# UI_Ticketing_Master.net
KiCad netlist of a schematic drawn in Altium Designer
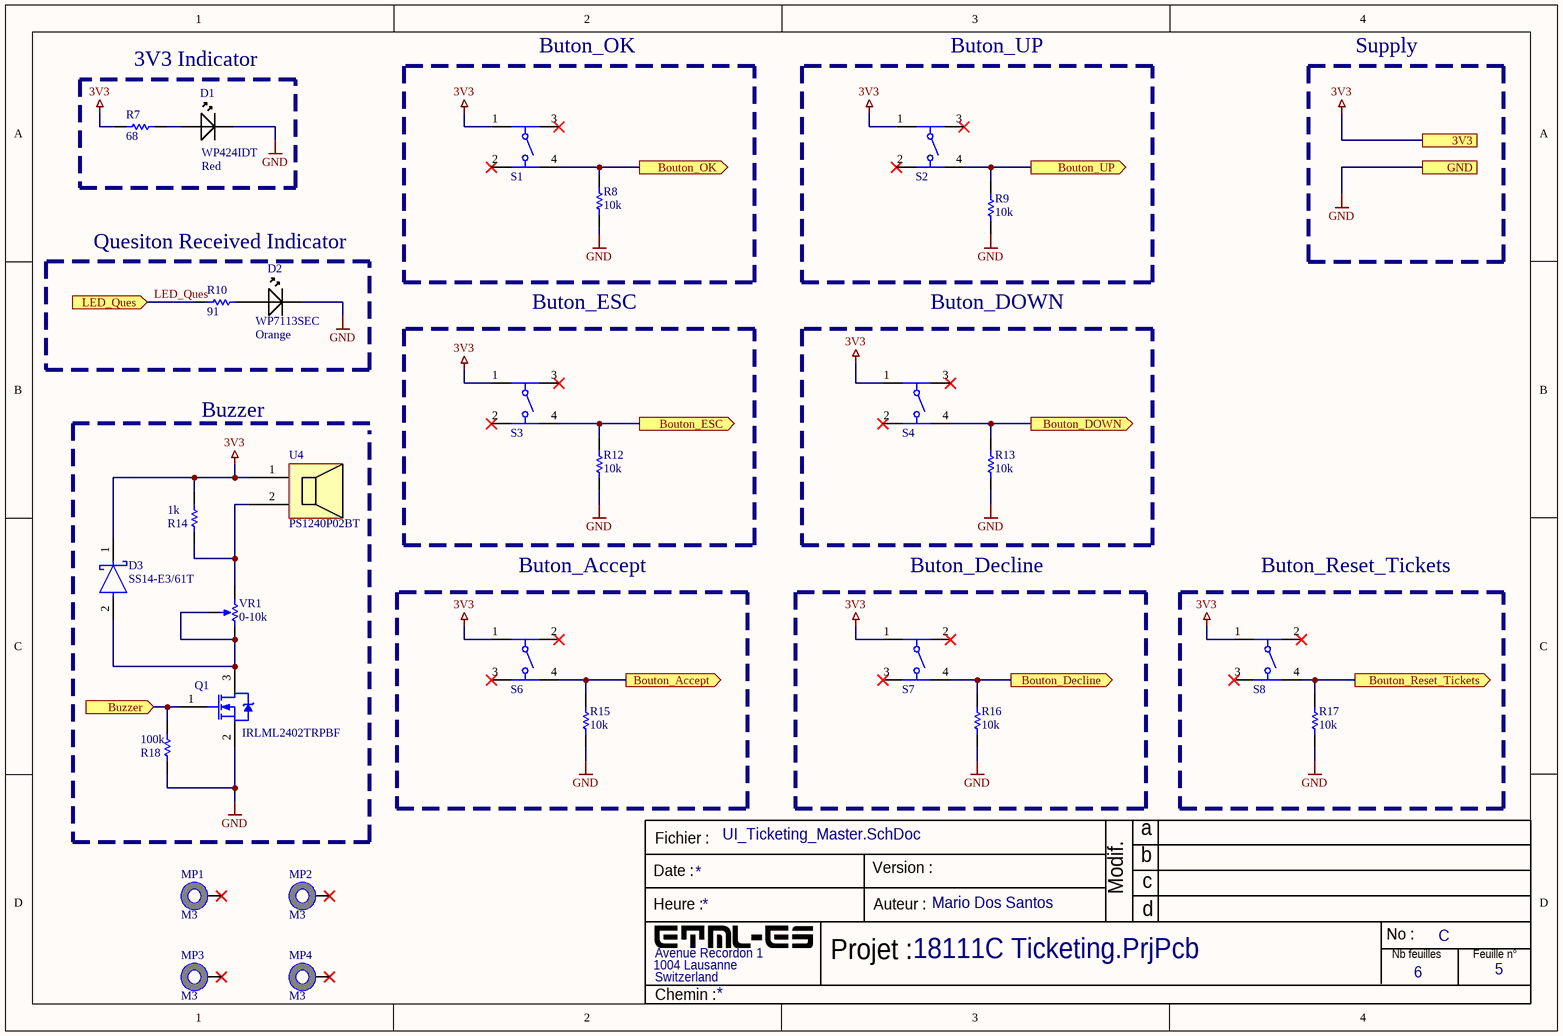
[diagram p0: UI_Ticketing_Master.SchDoc]

(export (version "E")
  (design (tool "Eeschema 10.0.6"))
  (components
    (comp (ref "D1")
      (value "WP424IDT")
      (footprint "LED-2P-2.28-3MM")
      (description "LED")
      (fields (field (name "COLOR") "Red"))
      (libsource (lib "") (part "LED_1"))
    )
    (comp (ref "D2")
      (value "WP7113SEC")
      (footprint "Type 5mm")
      (description "LED")
      (fields (field (name "COLOR") "Orange"))
      (libsource (lib "Spectrometre_Lib") (part "LED"))
    )
    (comp (ref "D3")
      (value "SS14-E3/61T")
      (footprint "FP-95400-MFG")
      (description "DIODE SCHOTTKY 40V 1A DO214AC")
      (fields
        (field (name "OCTOPART") "https://octopart.com/ss14-e3%2F61t-vishay-39552847")
        (field (name "MANUFACTURER") "Vishay")
      )
      (libsource (lib "Altium Content Vault") (part "1d6ec82d83fb6aee721767c19dac4b9"))
    )
    (comp (ref "MP1")
      (value "M3")
      (footprint "PCB_Ticketing_Master:9774010151")
      (description "WA-SMSI SMT Steel Spacer, M2.5 Thread Internal, Length 1mm")
      (libsource (lib "ALTIUM-SMSI_SMT_STEEL_SPACER_M2_5_THREAD_INTERNAL-rev16b") (part "9774010151"))
    )
    (comp (ref "MP2")
      (value "M3")
      (footprint "PCB_Ticketing_Master:9774010151")
      (description "WA-SMSI SMT Steel Spacer, M2.5 Thread Internal, Length 1mm")
      (libsource (lib "ALTIUM-SMSI_SMT_STEEL_SPACER_M2_5_THREAD_INTERNAL-rev16b") (part "9774010151"))
    )
    (comp (ref "MP3")
      (value "M3")
      (footprint "PCB_Ticketing_Master:9774010151")
      (description "WA-SMSI SMT Steel Spacer, M2.5 Thread Internal, Length 1mm")
      (libsource (lib "ALTIUM-SMSI_SMT_STEEL_SPACER_M2_5_THREAD_INTERNAL-rev16b") (part "9774010151"))
    )
    (comp (ref "MP4")
      (value "M3")
      (footprint "PCB_Ticketing_Master:9774010151")
      (description "WA-SMSI SMT Steel Spacer, M2.5 Thread Internal, Length 1mm")
      (libsource (lib "ALTIUM-SMSI_SMT_STEEL_SPACER_M2_5_THREAD_INTERNAL-rev16b") (part "9774010151"))
    )
    (comp (ref "Q1")
      (value "IRLML2402TRPBF")
      (footprint "INTR-IRLML2402TRPBF-3_V")
      (description "HEXFET(R) Power MOSFET, N-Channel, 20 V, 1.2 A, 3-Pin SOT-23, RoHS, Tape and Reel")
      (fields
        (field (name "MANUFACTURER") "Infineon Technologies")
        (field (name "PARTNUMBER") "IRLML2402TRBF")
      )
      (libsource (lib "Altium Content Vault") (part "CMP-2000-05155-1"))
    )
    (comp (ref "R7")
      (value "68")
      (footprint "RESC0805(2012)_L")
      (description "100K 0.125W 5% 0805 (2012 Metric)  SMD")
      (libsource (lib "Altium Content Vault") (part "CMP-1013-00122-1"))
    )
    (comp (ref "R8")
      (value "10k")
      (footprint "RESC0805(2012)_L")
      (description "100K 0.125W 5% 0805 (2012 Metric)  SMD")
      (fields (field (name "TOLERANCE") "5 %") (field (name "POWER") "0.125 W"))
      (libsource (lib "Altium Content Vault") (part "CMP-1013-00122-1"))
    )
    (comp (ref "R9")
      (value "10k")
      (footprint "RESC0805(2012)_L")
      (description "100K 0.125W 5% 0805 (2012 Metric)  SMD")
      (fields (field (name "TOLERANCE") "5 %") (field (name "POWER") "0.125 W"))
      (libsource (lib "Altium Content Vault") (part "CMP-1013-00122-1"))
    )
    (comp (ref "R10")
      (value "91")
      (footprint "RESC0805(2012)_L")
      (description "100K 0.125W 5% 0805 (2012 Metric)  SMD")
      (fields (field (name "TOLERANCE") "5 %") (field (name "POWER") "0.125 W"))
      (libsource (lib "Altium Content Vault") (part "CMP-1013-00122-1"))
    )
    (comp (ref "R12")
      (value "10k")
      (footprint "RESC0805(2012)_L")
      (description "100K 0.125W 5% 0805 (2012 Metric)  SMD")
      (fields (field (name "TOLERANCE") "5 %") (field (name "POWER") "0.125 W"))
      (libsource (lib "Altium Content Vault") (part "CMP-1013-00122-1"))
    )
    (comp (ref "R13")
      (value "10k")
      (footprint "RESC0805(2012)_L")
      (description "100K 0.125W 5% 0805 (2012 Metric)  SMD")
      (fields (field (name "TOLERANCE") "5 %") (field (name "POWER") "0.125 W"))
      (libsource (lib "Altium Content Vault") (part "CMP-1013-00122-1"))
    )
    (comp (ref "R14")
      (value "1k")
      (footprint "RESC2013X60X35ML10T20")
      (description "Chip Resistor, 1 KOhm, +/- 1%, 125 mW, -55 to 155 degC, 0805 (2012 Metric), RoHS, Tape and Reel")
      (libsource (lib "Altium Content Vault") (part "CMP-2100-03671-1"))
    )
    (comp (ref "R15")
      (value "10k")
      (footprint "RESC0805(2012)_L")
      (description "100K 0.125W 5% 0805 (2012 Metric)  SMD")
      (fields (field (name "TOLERANCE") "5 %") (field (name "POWER") "0.125 W"))
      (libsource (lib "Altium Content Vault") (part "CMP-1013-00122-1"))
    )
    (comp (ref "R16")
      (value "10k")
      (footprint "RESC0805(2012)_L")
      (description "100K 0.125W 5% 0805 (2012 Metric)  SMD")
      (fields (field (name "TOLERANCE") "5 %") (field (name "POWER") "0.125 W"))
      (libsource (lib "Altium Content Vault") (part "CMP-1013-00122-1"))
    )
    (comp (ref "R17")
      (value "10k")
      (footprint "RESC0805(2012)_L")
      (description "100K 0.125W 5% 0805 (2012 Metric)  SMD")
      (fields (field (name "TOLERANCE") "5 %") (field (name "POWER") "0.125 W"))
      (libsource (lib "Altium Content Vault") (part "CMP-1013-00122-1"))
    )
    (comp (ref "R18")
      (value "100k")
      (footprint "RESC2013X60X35ML10T20")
      (description "Chip Resistor, 100 KOhm, +/- 1%, 125 mW, -55 to 155 degC, 0805 (2012 Metric), RoHS, Tape and Reel")
      (libsource (lib "Altium Content Vault") (part "CMP-2100-03671-1"))
    )
    (comp (ref "S1")
      (value "430152095826")
      (footprint "430152095826")
      (description "6x6mm SMD Tact Switch WS-TASV, height 9.5 mm, 260 gf")
      (fields (field (name "PART NUMBER") "732-6999-1-ND") (field (name "PUBLISHER") "Wurth Elektronik"))
      (libsource (lib "ALTIUM-WS-TASV-rev17b") (part "430152095826"))
    )
    (comp (ref "S2")
      (value "430152095826")
      (footprint "430152095826")
      (description "6x6mm SMD Tact Switch WS-TASV, height 9.5 mm, 260 gf")
      (fields (field (name "PART NUMBER") "732-6999-1-ND") (field (name "PUBLISHER") "Wurth Elektronik"))
      (libsource (lib "ALTIUM-WS-TASV-rev17b") (part "430152095826"))
    )
    (comp (ref "S3")
      (value "430152095826")
      (footprint "430152095826")
      (description "6x6mm SMD Tact Switch WS-TASV, height 9.5 mm, 260 gf")
      (fields (field (name "PART NUMBER") "732-6999-1-ND") (field (name "PUBLISHER") "Wurth Elektronik"))
      (libsource (lib "ALTIUM-WS-TASV-rev17b") (part "430152095826"))
    )
    (comp (ref "S4")
      (value "430152095826")
      (footprint "430152095826")
      (description "6x6mm SMD Tact Switch WS-TASV, height 9.5 mm, 260 gf")
      (fields (field (name "PART NUMBER") "732-6999-1-ND") (field (name "PUBLISHER") "Wurth Elektronik"))
      (libsource (lib "ALTIUM-WS-TASV-rev17b") (part "430152095826"))
    )
    (comp (ref "S6")
      (value "430466073726")
      (footprint "4304x60737x6_12x12x7.3")
      (description "WS-TATV 12x12mm washable Tact Switch, THT version")
      (fields (field (name "PART NUMBER") "430466073726-ND") (field (name "PUBLISHER") "Wurth Elektronik"))
      (libsource (lib "ALTIUM-WS-TATV-rev17a") (part "430466073726"))
    )
    (comp (ref "S7")
      (value "430466073726")
      (footprint "4304x60737x6_12x12x7.3")
      (description "WS-TATV 12x12mm washable Tact Switch, THT version")
      (fields (field (name "PART NUMBER") "430466073726-ND") (field (name "PUBLISHER") "Wurth Elektronik"))
      (libsource (lib "ALTIUM-WS-TATV-rev17a") (part "430466073726"))
    )
    (comp (ref "S8")
      (value "430466073726")
      (footprint "4304x60737x6_12x12x7.3")
      (description "WS-TATV 12x12mm washable Tact Switch, THT version")
      (fields (field (name "PART NUMBER") "430466073726-ND") (field (name "PUBLISHER") "Wurth Elektronik"))
      (libsource (lib "ALTIUM-WS-TATV-rev17a") (part "430466073726"))
    )
    (comp (ref "U4")
      (value "PS1240P02BT")
      (footprint "Buzzer")
      (description "Buzzer 12mm piezo")
      (fields (field (name "MANUFACTURER") "TDK Corporation"))
      (libsource (lib "Schlib1") (part "BZR"))
    )
    (comp (ref "VR1")
      (value "0-10k")
      (footprint "BOUR-3362P")
      (description "Square Trimpot(R) Trimming Potentiometer, 100 KOhm, 300 V, -55 to 125 degC, 3-Pin THD, RoHS, Tube")
      (fields (field (name "TOLERANCE") "1%") (field (name "PART NUMBER") "3362P-103LF-ND"))
      (libsource (lib "Altium Content Vault") (part "CMP-1747-00003-1"))
    )
  )
  (nets
    (net (code "1") (name "/Bouton_Accept") (class "Default")
      (node (ref "R15") (pin "1") (pinfunction "1_1") (pintype "passive"))
      (node (ref "S6") (pin "4") (pinfunction "4_4") (pintype "passive"))
    )
    (net (code "2") (name "/Bouton_DOWN") (class "Default")
      (node (ref "R13") (pin "1") (pinfunction "1_1") (pintype "passive"))
      (node (ref "S4") (pin "4") (pinfunction "4_4") (pintype "passive"))
    )
    (net (code "3") (name "/Bouton_Decline") (class "Default")
      (node (ref "R16") (pin "1") (pinfunction "1_1") (pintype "passive"))
      (node (ref "S7") (pin "4") (pinfunction "4_4") (pintype "passive"))
    )
    (net (code "4") (name "/Bouton_ESC") (class "Default")
      (node (ref "R12") (pin "1") (pinfunction "1_1") (pintype "passive"))
      (node (ref "S3") (pin "4") (pinfunction "4_4") (pintype "passive"))
    )
    (net (code "5") (name "/Bouton_OK") (class "Default")
      (node (ref "R8") (pin "1") (pinfunction "1_1") (pintype "passive"))
      (node (ref "S1") (pin "4") (pinfunction "4_4") (pintype "passive"))
    )
    (net (code "6") (name "/Bouton_Reset_Tickets") (class "Default")
      (node (ref "R17") (pin "1") (pinfunction "1_1") (pintype "passive"))
      (node (ref "S8") (pin "4") (pinfunction "4_4") (pintype "passive"))
    )
    (net (code "7") (name "/Bouton_UP") (class "Default")
      (node (ref "R9") (pin "1") (pinfunction "1_1") (pintype "passive"))
      (node (ref "S2") (pin "4") (pinfunction "4_4") (pintype "passive"))
    )
    (net (code "8") (name "/Buzzer") (class "Default")
      (node (ref "Q1") (pin "1") (pinfunction "G_1") (pintype "passive"))
      (node (ref "R18") (pin "2") (pinfunction "2_2") (pintype "passive"))
    )
    (net (code "9") (name "/LED_Ques") (class "Default")
      (node (ref "R10") (pin "2") (pinfunction "2_2") (pintype "passive"))
    )
    (net (code "10") (name "3V3") (class "Default")
      (node (ref "D3") (pin "1") (pinfunction "C_1") (pintype "passive"))
      (node (ref "R14") (pin "2") (pinfunction "2_2") (pintype "passive"))
      (node (ref "R7") (pin "2") (pinfunction "2_2") (pintype "passive"))
      (node (ref "S1") (pin "1") (pinfunction "1_1") (pintype "passive"))
      (node (ref "S2") (pin "1") (pinfunction "1_1") (pintype "passive"))
      (node (ref "S3") (pin "1") (pinfunction "1_1") (pintype "passive"))
      (node (ref "S4") (pin "1") (pinfunction "1_1") (pintype "passive"))
      (node (ref "S6") (pin "1") (pinfunction "1_1") (pintype "passive"))
      (node (ref "S7") (pin "1") (pinfunction "1_1") (pintype "passive"))
      (node (ref "S8") (pin "1") (pinfunction "1_1") (pintype "passive"))
      (node (ref "U4") (pin "1") (pintype "passive"))
    )
    (net (code "11") (name "GND") (class "Default")
      (node (ref "D1") (pin "2") (pinfunction "Cathode_2") (pintype "passive"))
      (node (ref "D2") (pin "1") (pinfunction "Cathode_1") (pintype "passive"))
      (node (ref "Q1") (pin "2") (pinfunction "S_2") (pintype "passive"))
      (node (ref "R12") (pin "2") (pinfunction "2_2") (pintype "passive"))
      (node (ref "R13") (pin "2") (pinfunction "2_2") (pintype "passive"))
      (node (ref "R15") (pin "2") (pinfunction "2_2") (pintype "passive"))
      (node (ref "R16") (pin "2") (pinfunction "2_2") (pintype "passive"))
      (node (ref "R17") (pin "2") (pinfunction "2_2") (pintype "passive"))
      (node (ref "R18") (pin "1") (pinfunction "1_1") (pintype "passive"))
      (node (ref "R8") (pin "2") (pinfunction "2_2") (pintype "passive"))
      (node (ref "R9") (pin "2") (pinfunction "2_2") (pintype "passive"))
    )
    (net (code "12") (name "Net-(D1-Anode)") (class "Default")
      (node (ref "D1") (pin "1") (pinfunction "Anode_1") (pintype "passive"))
      (node (ref "R7") (pin "1") (pinfunction "1_1") (pintype "passive"))
    )
    (net (code "13") (name "Net-(D2-Anode)") (class "Default")
      (node (ref "D2") (pin "2") (pinfunction "Anode_2") (pintype "passive"))
      (node (ref "R10") (pin "1") (pinfunction "1_1") (pintype "passive"))
    )
    (net (code "14") (name "Net-(D3-A)") (class "Default")
      (node (ref "D3") (pin "2") (pinfunction "A_2") (pintype "passive"))
      (node (ref "Q1") (pin "3") (pinfunction "D_3") (pintype "passive"))
      (node (ref "VR1") (pin "2") (pinfunction "S_2") (pintype "passive"))
      (node (ref "VR1") (pin "3") (pinfunction "CW_3") (pintype "passive"))
    )
    (net (code "15") (name "Net-(VR1-CCW)") (class "Default")
      (node (ref "R14") (pin "1") (pinfunction "1_1") (pintype "passive"))
      (node (ref "U4") (pin "2") (pintype "passive"))
      (node (ref "VR1") (pin "1") (pinfunction "CCW_1") (pintype "passive"))
    )
    (net (code "16") (name "unconnected-(MP1-Pad1)") (class "Default")
      (node (ref "MP1") (pin "1") (pinfunction "1_1") (pintype "passive+no_connect"))
    )
    (net (code "17") (name "unconnected-(MP2-Pad1)") (class "Default")
      (node (ref "MP2") (pin "1") (pinfunction "1_1") (pintype "passive+no_connect"))
    )
    (net (code "18") (name "unconnected-(MP3-Pad1)") (class "Default")
      (node (ref "MP3") (pin "1") (pinfunction "1_1") (pintype "passive+no_connect"))
    )
    (net (code "19") (name "unconnected-(MP4-Pad1)") (class "Default")
      (node (ref "MP4") (pin "1") (pinfunction "1_1") (pintype "passive+no_connect"))
    )
    (net (code "20") (name "unconnected-(S1-Pad2)") (class "Default")
      (node (ref "S1") (pin "2") (pinfunction "2_2") (pintype "passive+no_connect"))
    )
    (net (code "21") (name "unconnected-(S1-Pad3)") (class "Default")
      (node (ref "S1") (pin "3") (pinfunction "3_3") (pintype "passive+no_connect"))
    )
    (net (code "22") (name "unconnected-(S2-Pad2)") (class "Default")
      (node (ref "S2") (pin "2") (pinfunction "2_2") (pintype "passive+no_connect"))
    )
    (net (code "23") (name "unconnected-(S2-Pad3)") (class "Default")
      (node (ref "S2") (pin "3") (pinfunction "3_3") (pintype "passive+no_connect"))
    )
    (net (code "24") (name "unconnected-(S3-Pad2)") (class "Default")
      (node (ref "S3") (pin "2") (pinfunction "2_2") (pintype "passive+no_connect"))
    )
    (net (code "25") (name "unconnected-(S3-Pad3)") (class "Default")
      (node (ref "S3") (pin "3") (pinfunction "3_3") (pintype "passive+no_connect"))
    )
    (net (code "26") (name "unconnected-(S4-Pad2)") (class "Default")
      (node (ref "S4") (pin "2") (pinfunction "2_2") (pintype "passive+no_connect"))
    )
    (net (code "27") (name "unconnected-(S4-Pad3)") (class "Default")
      (node (ref "S4") (pin "3") (pinfunction "3_3") (pintype "passive+no_connect"))
    )
    (net (code "28") (name "unconnected-(S6-Pad2)") (class "Default")
      (node (ref "S6") (pin "2") (pinfunction "2_2") (pintype "passive+no_connect"))
    )
    (net (code "29") (name "unconnected-(S6-Pad3)") (class "Default")
      (node (ref "S6") (pin "3") (pinfunction "3_3") (pintype "passive+no_connect"))
    )
    (net (code "30") (name "unconnected-(S7-Pad2)") (class "Default")
      (node (ref "S7") (pin "2") (pinfunction "2_2") (pintype "passive+no_connect"))
    )
    (net (code "31") (name "unconnected-(S7-Pad3)") (class "Default")
      (node (ref "S7") (pin "3") (pinfunction "3_3") (pintype "passive+no_connect"))
    )
    (net (code "32") (name "unconnected-(S8-Pad2)") (class "Default")
      (node (ref "S8") (pin "2") (pinfunction "2_2") (pintype "passive+no_connect"))
    )
    (net (code "33") (name "unconnected-(S8-Pad3)") (class "Default")
      (node (ref "S8") (pin "3") (pinfunction "3_3") (pintype "passive+no_connect"))
    )
  )
)
